# sch.net
KiCad netlist of a schematic drawn in EasyEDA
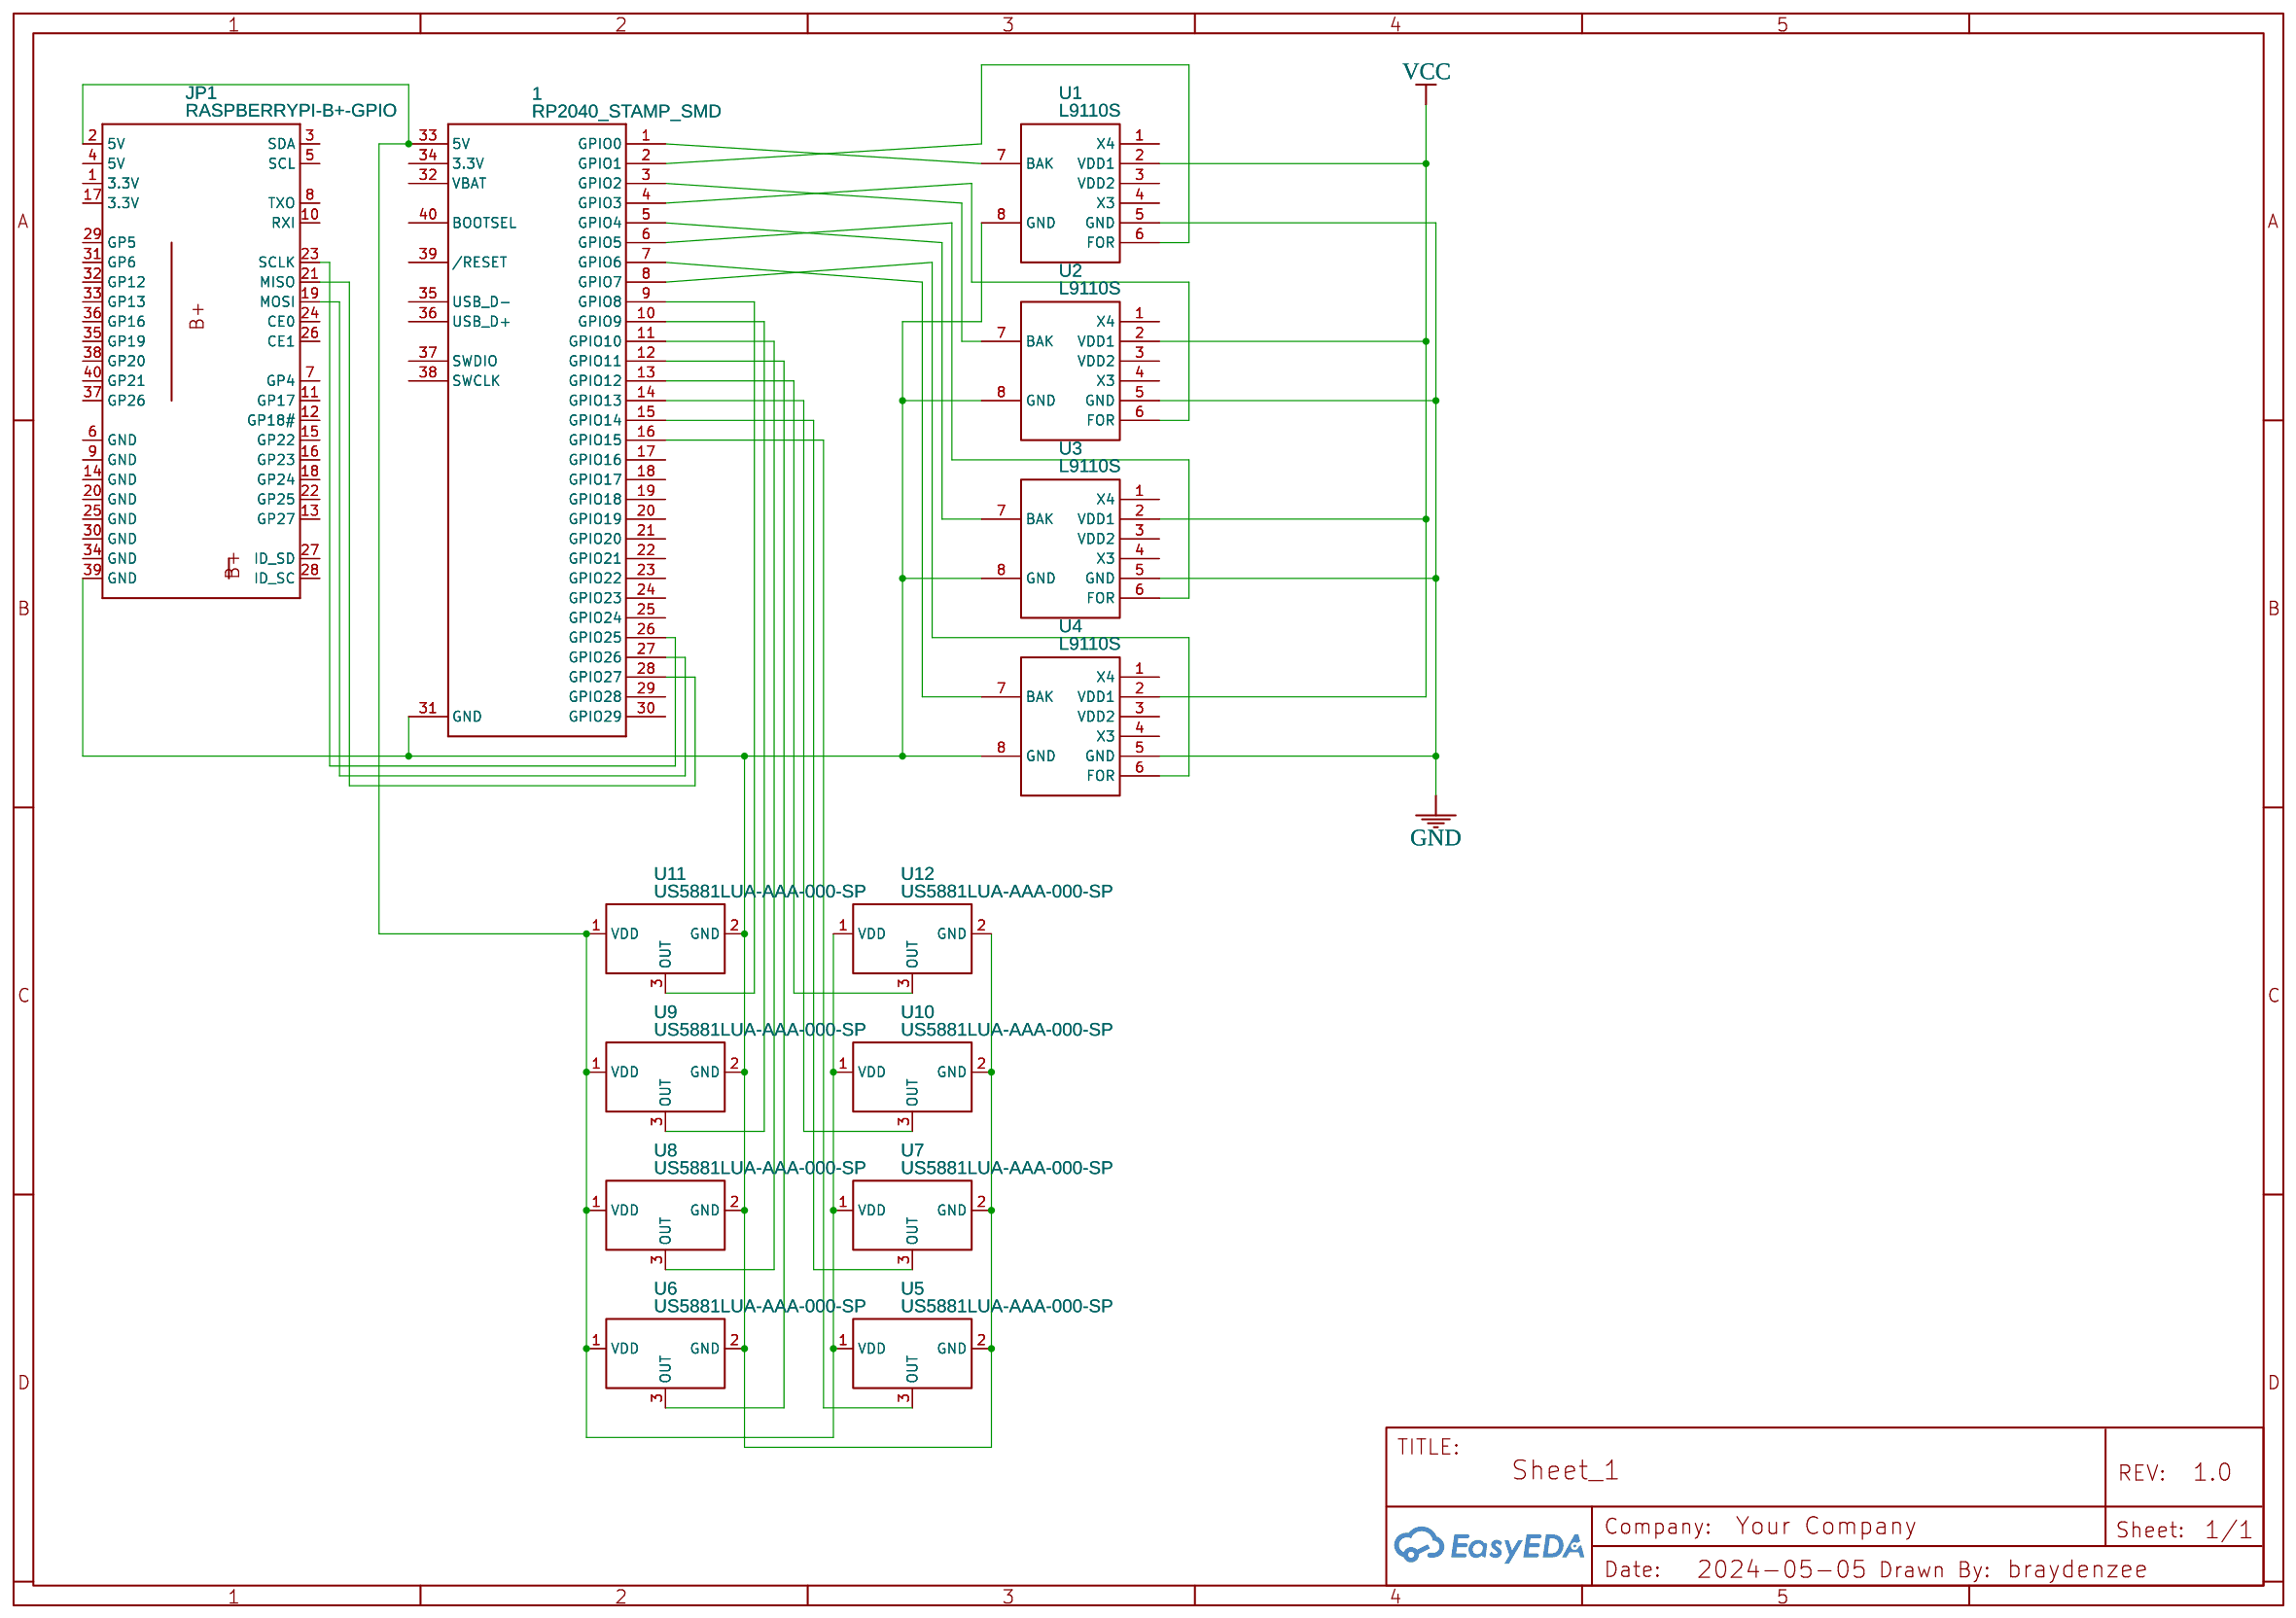
[diagram p0: schematic sheet]

(export (version "E")
  (design (tool "Eeschema 10.0.6"))
  (components
    (comp (ref "1") (value "RP2040_STAMP_SMD") (libsource (lib "") (part "RP2040_STAMP_SMD")))
    (comp (ref "JP1") (value "RASPBERRYPI-B+-GPIO") (libsource (lib "") (part "RASPBERRYPI-B+-GPIO")))
    (comp (ref "U1")
      (value "L9110S")
      (fields (field (name "Manufacturer") "I-CORE(中微爱芯)"))
      (libsource (lib "") (part "L9110S"))
    )
    (comp (ref "U2")
      (value "L9110S")
      (fields (field (name "Manufacturer") "I-CORE(中微爱芯)"))
      (libsource (lib "") (part "L9110S"))
    )
    (comp (ref "U3")
      (value "L9110S")
      (fields (field (name "Manufacturer") "I-CORE(中微爱芯)"))
      (libsource (lib "") (part "L9110S"))
    )
    (comp (ref "U4")
      (value "L9110S")
      (fields (field (name "Manufacturer") "I-CORE(中微爱芯)"))
      (libsource (lib "") (part "L9110S"))
    )
    (comp (ref "U5")
      (value "US5881LUA-AAA-000-SP")
      (fields (field (name "Manufacturer") "Melexis(比利时迈来芯)"))
      (libsource (lib "") (part "US5881LUA-AAA-000-SP"))
    )
    (comp (ref "U6")
      (value "US5881LUA-AAA-000-SP")
      (fields (field (name "Manufacturer") "Melexis(比利时迈来芯)"))
      (libsource (lib "") (part "US5881LUA-AAA-000-SP"))
    )
    (comp (ref "U7")
      (value "US5881LUA-AAA-000-SP")
      (fields (field (name "Manufacturer") "Melexis(比利时迈来芯)"))
      (libsource (lib "") (part "US5881LUA-AAA-000-SP"))
    )
    (comp (ref "U8")
      (value "US5881LUA-AAA-000-SP")
      (fields (field (name "Manufacturer") "Melexis(比利时迈来芯)"))
      (libsource (lib "") (part "US5881LUA-AAA-000-SP"))
    )
    (comp (ref "U9")
      (value "US5881LUA-AAA-000-SP")
      (fields (field (name "Manufacturer") "Melexis(比利时迈来芯)"))
      (libsource (lib "") (part "US5881LUA-AAA-000-SP"))
    )
    (comp (ref "U10")
      (value "US5881LUA-AAA-000-SP")
      (fields (field (name "Manufacturer") "Melexis(比利时迈来芯)"))
      (libsource (lib "") (part "US5881LUA-AAA-000-SP"))
    )
    (comp (ref "U11")
      (value "US5881LUA-AAA-000-SP")
      (fields (field (name "Manufacturer") "Melexis(比利时迈来芯)"))
      (libsource (lib "") (part "US5881LUA-AAA-000-SP"))
    )
    (comp (ref "U12")
      (value "US5881LUA-AAA-000-SP")
      (fields (field (name "Manufacturer") "Melexis(比利时迈来芯)"))
      (libsource (lib "") (part "US5881LUA-AAA-000-SP"))
    )
  )
  (nets
    (net (code "1") (name "GND") (class "Default")
      (node (ref "U1") (pin "5") (pinfunction "GND_5") (pintype "unspecified"))
      (node (ref "U2") (pin "5") (pinfunction "GND_5") (pintype "unspecified"))
      (node (ref "U3") (pin "5") (pinfunction "GND_5") (pintype "unspecified"))
      (node (ref "U4") (pin "5") (pinfunction "GND_5") (pintype "unspecified"))
    )
    (net (code "2") (name "Net-(1-5V)") (class "Default")
      (node (ref "1") (pin "33") (pinfunction "5V_33") (pintype "bidirectional"))
      (node (ref "JP1") (pin "2") (pinfunction "5V_2") (pintype "passive"))
      (node (ref "U10") (pin "1") (pinfunction "VDD_1") (pintype "unspecified"))
      (node (ref "U11") (pin "1") (pinfunction "VDD_1") (pintype "unspecified"))
      (node (ref "U12") (pin "1") (pinfunction "VDD_1") (pintype "unspecified"))
      (node (ref "U5") (pin "1") (pinfunction "VDD_1") (pintype "unspecified"))
      (node (ref "U6") (pin "1") (pinfunction "VDD_1") (pintype "unspecified"))
      (node (ref "U7") (pin "1") (pinfunction "VDD_1") (pintype "unspecified"))
      (node (ref "U8") (pin "1") (pinfunction "VDD_1") (pintype "unspecified"))
      (node (ref "U9") (pin "1") (pinfunction "VDD_1") (pintype "unspecified"))
    )
    (net (code "3") (name "Net-(1-GND)") (class "Default")
      (node (ref "1") (pin "31") (pinfunction "GND_31") (pintype "bidirectional"))
      (node (ref "JP1") (pin "39") (pinfunction "GND_39") (pintype "passive"))
      (node (ref "U1") (pin "8") (pinfunction "GND_8") (pintype "unspecified"))
      (node (ref "U10") (pin "2") (pinfunction "GND_2") (pintype "unspecified"))
      (node (ref "U11") (pin "2") (pinfunction "GND_2") (pintype "unspecified"))
      (node (ref "U12") (pin "2") (pinfunction "GND_2") (pintype "unspecified"))
      (node (ref "U2") (pin "8") (pinfunction "GND_8") (pintype "unspecified"))
      (node (ref "U3") (pin "8") (pinfunction "GND_8") (pintype "unspecified"))
      (node (ref "U4") (pin "8") (pinfunction "GND_8") (pintype "unspecified"))
      (node (ref "U5") (pin "2") (pinfunction "GND_2") (pintype "unspecified"))
      (node (ref "U6") (pin "2") (pinfunction "GND_2") (pintype "unspecified"))
      (node (ref "U7") (pin "2") (pinfunction "GND_2") (pintype "unspecified"))
      (node (ref "U8") (pin "2") (pinfunction "GND_2") (pintype "unspecified"))
      (node (ref "U9") (pin "2") (pinfunction "GND_2") (pintype "unspecified"))
    )
    (net (code "4") (name "Net-(1-GPIO0)") (class "Default")
      (node (ref "1") (pin "1") (pinfunction "GPIO0_1") (pintype "bidirectional"))
      (node (ref "U1") (pin "7") (pinfunction "BAK_7") (pintype "unspecified"))
    )
    (net (code "5") (name "Net-(1-GPIO1)") (class "Default")
      (node (ref "1") (pin "2") (pinfunction "GPIO1_2") (pintype "bidirectional"))
      (node (ref "U1") (pin "6") (pinfunction "FOR_6") (pintype "unspecified"))
    )
    (net (code "6") (name "Net-(1-GPIO2)") (class "Default")
      (node (ref "1") (pin "3") (pinfunction "GPIO2_3") (pintype "bidirectional"))
      (node (ref "U2") (pin "7") (pinfunction "BAK_7") (pintype "unspecified"))
    )
    (net (code "7") (name "Net-(1-GPIO3)") (class "Default")
      (node (ref "1") (pin "4") (pinfunction "GPIO3_4") (pintype "bidirectional"))
      (node (ref "U2") (pin "6") (pinfunction "FOR_6") (pintype "unspecified"))
    )
    (net (code "8") (name "Net-(1-GPIO4)") (class "Default")
      (node (ref "1") (pin "5") (pinfunction "GPIO4_5") (pintype "bidirectional"))
      (node (ref "U3") (pin "7") (pinfunction "BAK_7") (pintype "unspecified"))
    )
    (net (code "9") (name "Net-(1-GPIO5)") (class "Default")
      (node (ref "1") (pin "6") (pinfunction "GPIO5_6") (pintype "bidirectional"))
      (node (ref "U3") (pin "6") (pinfunction "FOR_6") (pintype "unspecified"))
    )
    (net (code "10") (name "Net-(1-GPIO6)") (class "Default")
      (node (ref "1") (pin "7") (pinfunction "GPIO6_7") (pintype "bidirectional"))
      (node (ref "U4") (pin "7") (pinfunction "BAK_7") (pintype "unspecified"))
    )
    (net (code "11") (name "Net-(1-GPIO7)") (class "Default")
      (node (ref "1") (pin "8") (pinfunction "GPIO7_8") (pintype "bidirectional"))
      (node (ref "U4") (pin "6") (pinfunction "FOR_6") (pintype "unspecified"))
    )
    (net (code "12") (name "Net-(1-GPIO8)") (class "Default")
      (node (ref "1") (pin "9") (pinfunction "GPIO8_9") (pintype "bidirectional"))
      (node (ref "U11") (pin "3") (pinfunction "OUT_3") (pintype "unspecified"))
    )
    (net (code "13") (name "Net-(1-GPIO9)") (class "Default")
      (node (ref "1") (pin "10") (pinfunction "GPIO9_10") (pintype "bidirectional"))
      (node (ref "U9") (pin "3") (pinfunction "OUT_3") (pintype "unspecified"))
    )
    (net (code "14") (name "Net-(1-GPIO10)") (class "Default")
      (node (ref "1") (pin "11") (pinfunction "GPIO10_11") (pintype "bidirectional"))
      (node (ref "U8") (pin "3") (pinfunction "OUT_3") (pintype "unspecified"))
    )
    (net (code "15") (name "Net-(1-GPIO11)") (class "Default")
      (node (ref "1") (pin "12") (pinfunction "GPIO11_12") (pintype "bidirectional"))
      (node (ref "U6") (pin "3") (pinfunction "OUT_3") (pintype "unspecified"))
    )
    (net (code "16") (name "Net-(1-GPIO12)") (class "Default")
      (node (ref "1") (pin "13") (pinfunction "GPIO12_13") (pintype "bidirectional"))
      (node (ref "U12") (pin "3") (pinfunction "OUT_3") (pintype "unspecified"))
    )
    (net (code "17") (name "Net-(1-GPIO13)") (class "Default")
      (node (ref "1") (pin "14") (pinfunction "GPIO13_14") (pintype "bidirectional"))
      (node (ref "U10") (pin "3") (pinfunction "OUT_3") (pintype "unspecified"))
    )
    (net (code "18") (name "Net-(1-GPIO14)") (class "Default")
      (node (ref "1") (pin "15") (pinfunction "GPIO14_15") (pintype "bidirectional"))
      (node (ref "U7") (pin "3") (pinfunction "OUT_3") (pintype "unspecified"))
    )
    (net (code "19") (name "Net-(1-GPIO15)") (class "Default")
      (node (ref "1") (pin "16") (pinfunction "GPIO15_16") (pintype "bidirectional"))
      (node (ref "U5") (pin "3") (pinfunction "OUT_3") (pintype "unspecified"))
    )
    (net (code "20") (name "Net-(1-GPIO25)") (class "Default")
      (node (ref "1") (pin "26") (pinfunction "GPIO25_26") (pintype "bidirectional"))
      (node (ref "JP1") (pin "23") (pinfunction "SCLK_23") (pintype "output"))
    )
    (net (code "21") (name "Net-(1-GPIO26)") (class "Default")
      (node (ref "1") (pin "27") (pinfunction "GPIO26_27") (pintype "bidirectional"))
      (node (ref "JP1") (pin "19") (pinfunction "MOSI_19") (pintype "output"))
    )
    (net (code "22") (name "Net-(1-GPIO27)") (class "Default")
      (node (ref "1") (pin "28") (pinfunction "GPIO27_28") (pintype "bidirectional"))
      (node (ref "JP1") (pin "21") (pinfunction "MISO_21") (pintype "input"))
    )
    (net (code "23") (name "VCC") (class "Default")
      (node (ref "U1") (pin "2") (pinfunction "VDD1_2") (pintype "unspecified"))
      (node (ref "U2") (pin "2") (pinfunction "VDD1_2") (pintype "unspecified"))
      (node (ref "U3") (pin "2") (pinfunction "VDD1_2") (pintype "unspecified"))
      (node (ref "U4") (pin "2") (pinfunction "VDD1_2") (pintype "unspecified"))
    )
    (net (code "24") (name "unconnected-(1-3.3V-Pad34)") (class "Default")
      (node (ref "1") (pin "34") (pinfunction "3.3V_34") (pintype "bidirectional"))
    )
    (net (code "25") (name "unconnected-(1-BOOTSEL-Pad40)") (class "Default")
      (node (ref "1") (pin "40") (pinfunction "BOOTSEL_40") (pintype "bidirectional"))
    )
    (net (code "26") (name "unconnected-(1-GPIO16-Pad17)") (class "Default")
      (node (ref "1") (pin "17") (pinfunction "GPIO16_17") (pintype "bidirectional"))
    )
    (net (code "27") (name "unconnected-(1-GPIO17-Pad18)") (class "Default")
      (node (ref "1") (pin "18") (pinfunction "GPIO17_18") (pintype "bidirectional"))
    )
    (net (code "28") (name "unconnected-(1-GPIO18-Pad19)") (class "Default")
      (node (ref "1") (pin "19") (pinfunction "GPIO18_19") (pintype "bidirectional"))
    )
    (net (code "29") (name "unconnected-(1-GPIO19-Pad20)") (class "Default")
      (node (ref "1") (pin "20") (pinfunction "GPIO19_20") (pintype "bidirectional"))
    )
    (net (code "30") (name "unconnected-(1-GPIO20-Pad21)") (class "Default")
      (node (ref "1") (pin "21") (pinfunction "GPIO20_21") (pintype "bidirectional"))
    )
    (net (code "31") (name "unconnected-(1-GPIO21-Pad22)") (class "Default")
      (node (ref "1") (pin "22") (pinfunction "GPIO21_22") (pintype "bidirectional"))
    )
    (net (code "32") (name "unconnected-(1-GPIO22-Pad23)") (class "Default")
      (node (ref "1") (pin "23") (pinfunction "GPIO22_23") (pintype "bidirectional"))
    )
    (net (code "33") (name "unconnected-(1-GPIO23-Pad24)") (class "Default")
      (node (ref "1") (pin "24") (pinfunction "GPIO23_24") (pintype "bidirectional"))
    )
    (net (code "34") (name "unconnected-(1-GPIO24-Pad25)") (class "Default")
      (node (ref "1") (pin "25") (pinfunction "GPIO24_25") (pintype "bidirectional"))
    )
    (net (code "35") (name "unconnected-(1-GPIO28-Pad29)") (class "Default")
      (node (ref "1") (pin "29") (pinfunction "GPIO28_29") (pintype "bidirectional"))
    )
    (net (code "36") (name "unconnected-(1-GPIO29-Pad30)") (class "Default")
      (node (ref "1") (pin "30") (pinfunction "GPIO29_30") (pintype "bidirectional"))
    )
    (net (code "37") (name "unconnected-(1-SWCLK-Pad38)") (class "Default")
      (node (ref "1") (pin "38") (pinfunction "SWCLK_38") (pintype "bidirectional"))
    )
    (net (code "38") (name "unconnected-(1-SWDIO-Pad37)") (class "Default")
      (node (ref "1") (pin "37") (pinfunction "SWDIO_37") (pintype "bidirectional"))
    )
    (net (code "39") (name "unconnected-(1-USB_D+-Pad36)") (class "Default")
      (node (ref "1") (pin "36") (pinfunction "USB_D+_36") (pintype "bidirectional"))
    )
    (net (code "40") (name "unconnected-(1-USB_D--Pad35)") (class "Default")
      (node (ref "1") (pin "35") (pinfunction "USB_D-_35") (pintype "bidirectional"))
    )
    (net (code "41") (name "unconnected-(1-VBAT-Pad32)") (class "Default")
      (node (ref "1") (pin "32") (pinfunction "VBAT_32") (pintype "bidirectional"))
    )
    (net (code "42") (name "unconnected-(1-{slash}RESET-Pad39)") (class "Default")
      (node (ref "1") (pin "39") (pinfunction "/RESET_39") (pintype "bidirectional"))
    )
    (net (code "43") (name "unconnected-(JP1-3.3V-Pad1)") (class "Default")
      (node (ref "JP1") (pin "1") (pinfunction "3.3V_1") (pintype "passive"))
    )
    (net (code "44") (name "unconnected-(JP1-3.3V-Pad17)") (class "Default")
      (node (ref "JP1") (pin "17") (pinfunction "3.3V_17") (pintype "passive"))
    )
    (net (code "45") (name "unconnected-(JP1-5V-Pad4)") (class "Default")
      (node (ref "JP1") (pin "4") (pinfunction "5V_4") (pintype "passive"))
    )
    (net (code "46") (name "unconnected-(JP1-CE0-Pad24)") (class "Default")
      (node (ref "JP1") (pin "24") (pinfunction "CE0_24") (pintype "output"))
    )
    (net (code "47") (name "unconnected-(JP1-CE1-Pad26)") (class "Default")
      (node (ref "JP1") (pin "26") (pinfunction "CE1_26") (pintype "output"))
    )
    (net (code "48") (name "unconnected-(JP1-GND-Pad6)") (class "Default")
      (node (ref "JP1") (pin "6") (pinfunction "GND_6") (pintype "passive"))
    )
    (net (code "49") (name "unconnected-(JP1-GND-Pad9)") (class "Default")
      (node (ref "JP1") (pin "9") (pinfunction "GND_9") (pintype "passive"))
    )
    (net (code "50") (name "unconnected-(JP1-GND-Pad14)") (class "Default")
      (node (ref "JP1") (pin "14") (pinfunction "GND_14") (pintype "passive"))
    )
    (net (code "51") (name "unconnected-(JP1-GND-Pad20)") (class "Default")
      (node (ref "JP1") (pin "20") (pinfunction "GND_20") (pintype "passive"))
    )
    (net (code "52") (name "unconnected-(JP1-GND-Pad25)") (class "Default")
      (node (ref "JP1") (pin "25") (pinfunction "GND_25") (pintype "passive"))
    )
    (net (code "53") (name "unconnected-(JP1-GND-Pad30)") (class "Default")
      (node (ref "JP1") (pin "30") (pinfunction "GND_30") (pintype "passive"))
    )
    (net (code "54") (name "unconnected-(JP1-GND-Pad34)") (class "Default")
      (node (ref "JP1") (pin "34") (pinfunction "GND_34") (pintype "passive"))
    )
    (net (code "55") (name "unconnected-(JP1-GP4-Pad7)") (class "Default")
      (node (ref "JP1") (pin "7") (pinfunction "GP4_7") (pintype "unspecified"))
    )
    (net (code "56") (name "unconnected-(JP1-GP5-Pad29)") (class "Default")
      (node (ref "JP1") (pin "29") (pinfunction "GP5_29") (pintype "unspecified"))
    )
    (net (code "57") (name "unconnected-(JP1-GP6-Pad31)") (class "Default")
      (node (ref "JP1") (pin "31") (pinfunction "GP6_31") (pintype "unspecified"))
    )
    (net (code "58") (name "unconnected-(JP1-GP12-Pad32)") (class "Default")
      (node (ref "JP1") (pin "32") (pinfunction "GP12_32") (pintype "unspecified"))
    )
    (net (code "59") (name "unconnected-(JP1-GP13-Pad33)") (class "Default")
      (node (ref "JP1") (pin "33") (pinfunction "GP13_33") (pintype "unspecified"))
    )
    (net (code "60") (name "unconnected-(JP1-GP16-Pad36)") (class "Default")
      (node (ref "JP1") (pin "36") (pinfunction "GP16_36") (pintype "unspecified"))
    )
    (net (code "61") (name "unconnected-(JP1-GP17-Pad11)") (class "Default")
      (node (ref "JP1") (pin "11") (pinfunction "GP17_11") (pintype "unspecified"))
    )
    (net (code "62") (name "unconnected-(JP1-GP18#-Pad12)") (class "Default")
      (node (ref "JP1") (pin "12") (pinfunction "GP18#_12") (pintype "unspecified"))
    )
    (net (code "63") (name "unconnected-(JP1-GP19-Pad35)") (class "Default")
      (node (ref "JP1") (pin "35") (pinfunction "GP19_35") (pintype "unspecified"))
    )
    (net (code "64") (name "unconnected-(JP1-GP20-Pad38)") (class "Default")
      (node (ref "JP1") (pin "38") (pinfunction "GP20_38") (pintype "unspecified"))
    )
    (net (code "65") (name "unconnected-(JP1-GP21-Pad40)") (class "Default")
      (node (ref "JP1") (pin "40") (pinfunction "GP21_40") (pintype "unspecified"))
    )
    (net (code "66") (name "unconnected-(JP1-GP22-Pad15)") (class "Default")
      (node (ref "JP1") (pin "15") (pinfunction "GP22_15") (pintype "unspecified"))
    )
    (net (code "67") (name "unconnected-(JP1-GP23-Pad16)") (class "Default")
      (node (ref "JP1") (pin "16") (pinfunction "GP23_16") (pintype "unspecified"))
    )
    (net (code "68") (name "unconnected-(JP1-GP24-Pad18)") (class "Default")
      (node (ref "JP1") (pin "18") (pinfunction "GP24_18") (pintype "unspecified"))
    )
    (net (code "69") (name "unconnected-(JP1-GP25-Pad22)") (class "Default")
      (node (ref "JP1") (pin "22") (pinfunction "GP25_22") (pintype "unspecified"))
    )
    (net (code "70") (name "unconnected-(JP1-GP26-Pad37)") (class "Default")
      (node (ref "JP1") (pin "37") (pinfunction "GP26_37") (pintype "unspecified"))
    )
    (net (code "71") (name "unconnected-(JP1-GP27-Pad13)") (class "Default")
      (node (ref "JP1") (pin "13") (pinfunction "GP27_13") (pintype "unspecified"))
    )
    (net (code "72") (name "unconnected-(JP1-ID_SC-Pad28)") (class "Default")
      (node (ref "JP1") (pin "28") (pinfunction "ID_SC_28") (pintype "unspecified"))
    )
    (net (code "73") (name "unconnected-(JP1-ID_SD-Pad27)") (class "Default")
      (node (ref "JP1") (pin "27") (pinfunction "ID_SD_27") (pintype "unspecified"))
    )
    (net (code "74") (name "unconnected-(JP1-RXI-Pad10)") (class "Default")
      (node (ref "JP1") (pin "10") (pinfunction "RXI_10") (pintype "input"))
    )
    (net (code "75") (name "unconnected-(JP1-SCL-Pad5)") (class "Default")
      (node (ref "JP1") (pin "5") (pinfunction "SCL_5") (pintype "unspecified"))
    )
    (net (code "76") (name "unconnected-(JP1-SDA-Pad3)") (class "Default")
      (node (ref "JP1") (pin "3") (pinfunction "SDA_3") (pintype "unspecified"))
    )
    (net (code "77") (name "unconnected-(JP1-TXO-Pad8)") (class "Default")
      (node (ref "JP1") (pin "8") (pinfunction "TXO_8") (pintype "output"))
    )
    (net (code "78") (name "unconnected-(U1-VDD2-Pad3)") (class "Default")
      (node (ref "U1") (pin "3") (pinfunction "VDD2_3") (pintype "unspecified"))
    )
    (net (code "79") (name "unconnected-(U1-X3-Pad4)") (class "Default")
      (node (ref "U1") (pin "4") (pinfunction "X3_4") (pintype "passive"))
    )
    (net (code "80") (name "unconnected-(U1-X4-Pad1)") (class "Default")
      (node (ref "U1") (pin "1") (pinfunction "X4_1") (pintype "unspecified"))
    )
    (net (code "81") (name "unconnected-(U2-VDD2-Pad3)") (class "Default")
      (node (ref "U2") (pin "3") (pinfunction "VDD2_3") (pintype "unspecified"))
    )
    (net (code "82") (name "unconnected-(U2-X3-Pad4)") (class "Default")
      (node (ref "U2") (pin "4") (pinfunction "X3_4") (pintype "passive"))
    )
    (net (code "83") (name "unconnected-(U2-X4-Pad1)") (class "Default")
      (node (ref "U2") (pin "1") (pinfunction "X4_1") (pintype "unspecified"))
    )
    (net (code "84") (name "unconnected-(U3-VDD2-Pad3)") (class "Default")
      (node (ref "U3") (pin "3") (pinfunction "VDD2_3") (pintype "unspecified"))
    )
    (net (code "85") (name "unconnected-(U3-X3-Pad4)") (class "Default")
      (node (ref "U3") (pin "4") (pinfunction "X3_4") (pintype "passive"))
    )
    (net (code "86") (name "unconnected-(U3-X4-Pad1)") (class "Default")
      (node (ref "U3") (pin "1") (pinfunction "X4_1") (pintype "unspecified"))
    )
    (net (code "87") (name "unconnected-(U4-VDD2-Pad3)") (class "Default")
      (node (ref "U4") (pin "3") (pinfunction "VDD2_3") (pintype "unspecified"))
    )
    (net (code "88") (name "unconnected-(U4-X3-Pad4)") (class "Default")
      (node (ref "U4") (pin "4") (pinfunction "X3_4") (pintype "passive"))
    )
    (net (code "89") (name "unconnected-(U4-X4-Pad1)") (class "Default")
      (node (ref "U4") (pin "1") (pinfunction "X4_1") (pintype "unspecified"))
    )
  )
)
